# GlucometerV2_3.net
KiCad netlist of a schematic drawn in EAGLE
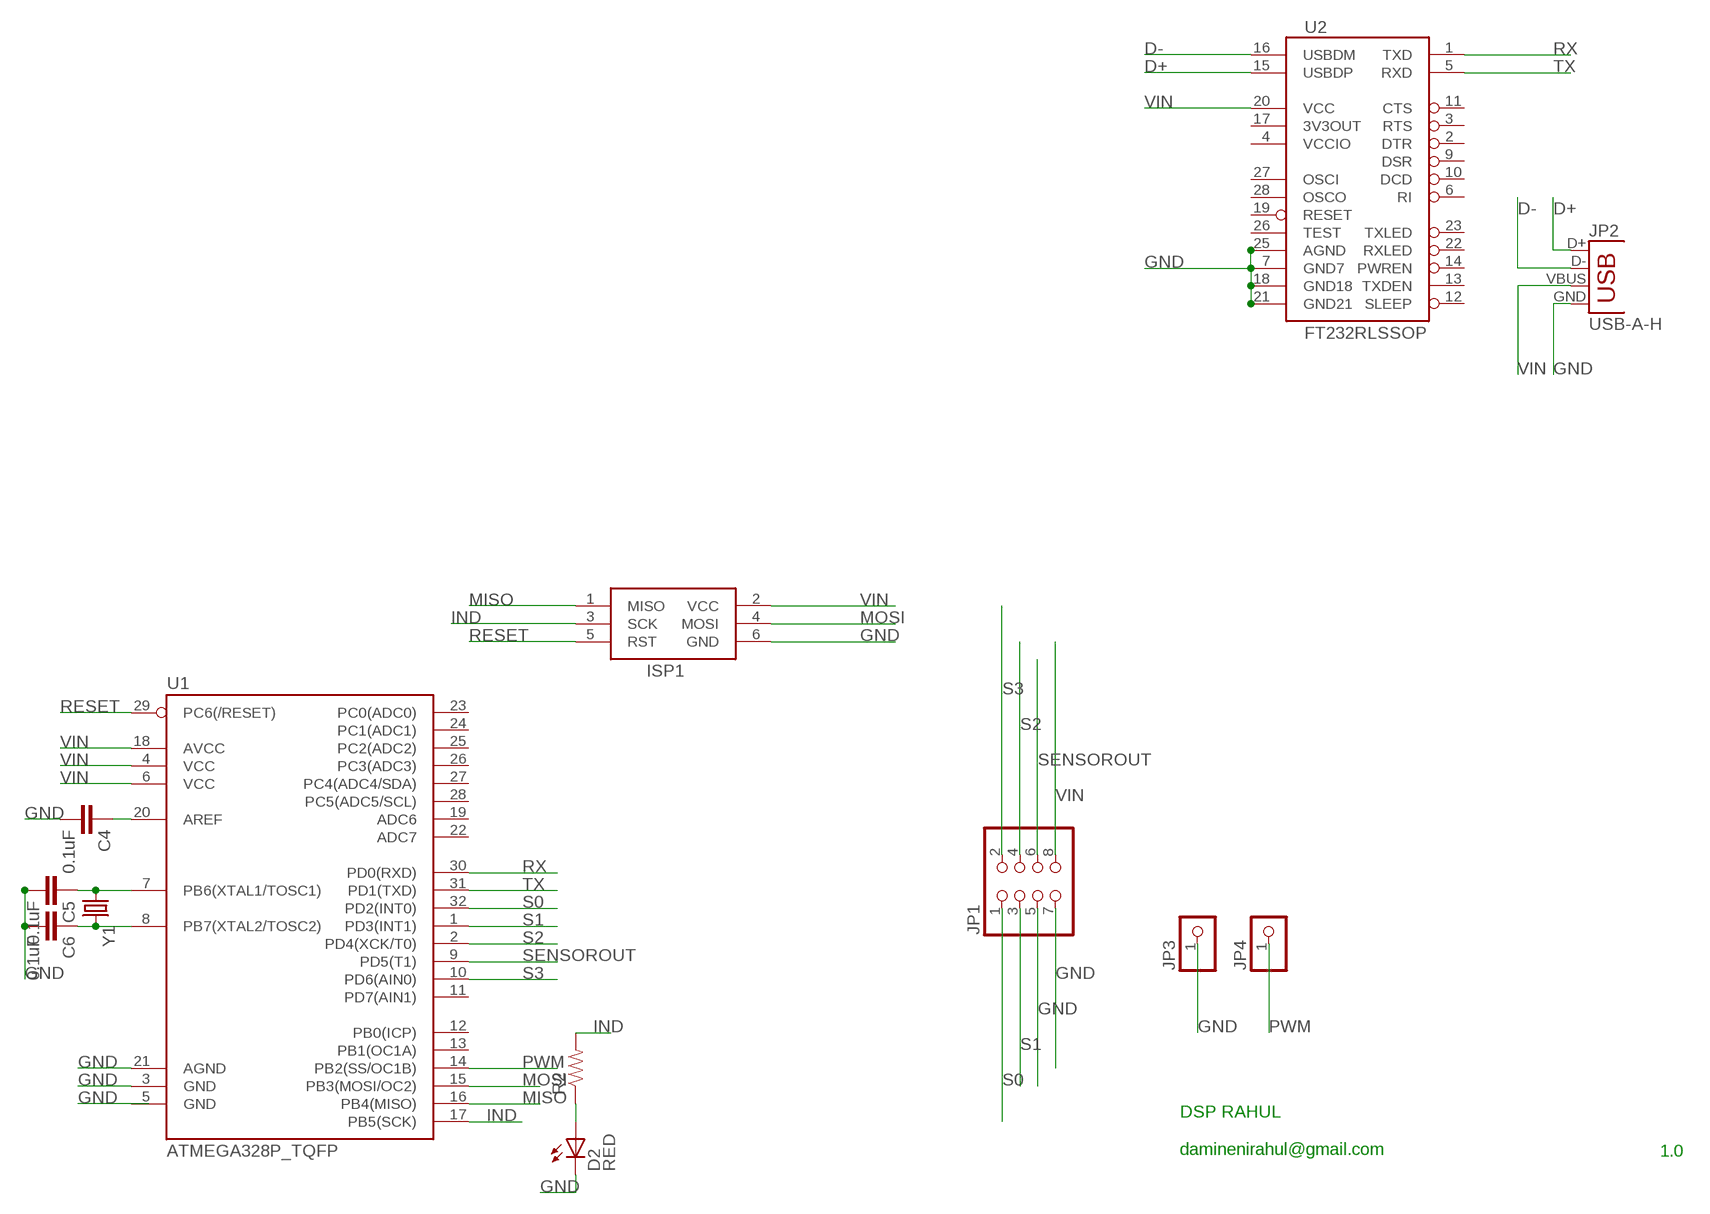
[diagram p0: schematic, sheet 1]

(export (version "E")
  (design (tool "Eeschema 10.0.6"))
  (components
    (comp (ref "C4")
      (value "0.1uF")
      (footprint "eagle-import:0603-CAP")
      (libsource (lib "eagle-import") (part "0.1UF-25V(+80/-20%)(0603)"))
    )
    (comp (ref "C5")
      (value "0.1uF")
      (footprint "eagle-import:0603-CAP")
      (libsource (lib "eagle-import") (part "0.1UF-25V(+80/-20%)(0603)"))
    )
    (comp (ref "C6")
      (value "0.1uF")
      (footprint "eagle-import:0603-CAP")
      (libsource (lib "eagle-import") (part "0.1UF-25V(+80/-20%)(0603)"))
    )
    (comp (ref "D2")
      (value "RED")
      (footprint "eagle-import:CHIPLED_1206")
      (libsource (lib "eagle-import") (part "LEDCHIPLED_1206"))
    )
    (comp (ref "ISP1")
      (value "AVRISP-6")
      (footprint "eagle-import:AVRISP")
      (libsource (lib "eagle-import") (part "AVRISP-6"))
    )
    (comp (ref "JP1")
      (value "PINHD-2X4")
      (footprint "eagle-import:2X04")
      (libsource (lib "eagle-import") (part "PINHD-2X4"))
    )
    (comp (ref "JP2")
      (value "USB-A-H")
      (footprint "eagle-import:USB-A-H")
      (libsource (lib "eagle-import") (part "USB-A-H"))
    )
    (comp (ref "JP3")
      (value "PINHD-1X1")
      (footprint "eagle-import:1X01")
      (libsource (lib "eagle-import") (part "PINHD-1X1"))
    )
    (comp (ref "JP4")
      (value "PINHD-1X1")
      (footprint "eagle-import:1X01")
      (libsource (lib "eagle-import") (part "PINHD-1X1"))
    )
    (comp (ref "R2")
      (value "RESISTOR1206")
      (footprint "eagle-import:1206")
      (libsource (lib "eagle-import") (part "RESISTOR1206"))
    )
    (comp (ref "U1")
      (value "ATMEGA328P_TQFP")
      (footprint "eagle-import:TQFP32-08")
      (libsource (lib "eagle-import") (part "ATMEGA328P_TQFP"))
    )
    (comp (ref "U2")
      (value "FT232RLSSOP")
      (footprint "eagle-import:SSOP28DB")
      (libsource (lib "eagle-import") (part "FT232RLSSOP"))
    )
    (comp (ref "Y1")
      (value "CRYSTALHC49UV")
      (footprint "eagle-import:HC49U-V")
      (libsource (lib "eagle-import") (part "CRYSTALHC49UV"))
    )
  )
  (nets
    (net (code "1") (name "/D+") (class "Default")
      (node (ref "JP2") (pin "D+") (pinfunction "D+_D+") (pintype "bidirectional"))
      (node (ref "U2") (pin "15") (pinfunction "USBDP_15") (pintype "bidirectional"))
    )
    (net (code "2") (name "/D-") (class "Default")
      (node (ref "JP2") (pin "D-") (pinfunction "D-_D-") (pintype "bidirectional"))
      (node (ref "U2") (pin "16") (pinfunction "USBDM_16") (pintype "bidirectional"))
    )
    (net (code "3") (name "/GND") (class "Default")
      (node (ref "C4") (pin "2") (pinfunction "2_2") (pintype "passive"))
      (node (ref "C5") (pin "2") (pinfunction "2_2") (pintype "passive"))
      (node (ref "C6") (pin "2") (pinfunction "2_2") (pintype "passive"))
      (node (ref "D2") (pin "C") (pinfunction "C_C") (pintype "passive"))
      (node (ref "ISP1") (pin "6") (pinfunction "GND_6") (pintype "power_in"))
      (node (ref "JP1") (pin "5") (pinfunction "5_5") (pintype "passive"))
      (node (ref "JP1") (pin "7") (pinfunction "7_7") (pintype "passive"))
      (node (ref "JP2") (pin "GND") (pinfunction "GND_GND") (pintype "bidirectional"))
      (node (ref "JP3") (pin "1") (pinfunction "1_1") (pintype "passive"))
      (node (ref "U1") (pin "21") (pinfunction "AGND_21") (pintype "bidirectional"))
      (node (ref "U1") (pin "3") (pinfunction "GND_3") (pintype "bidirectional"))
      (node (ref "U2") (pin "18") (pinfunction "GND18_18") (pintype "power_in"))
      (node (ref "U2") (pin "21") (pinfunction "GND21_21") (pintype "power_in"))
      (node (ref "U2") (pin "25") (pinfunction "AGND_25") (pintype "power_in"))
      (node (ref "U2") (pin "7") (pinfunction "GND7_7") (pintype "power_in"))
    )
    (net (code "4") (name "/IND") (class "Default")
      (node (ref "ISP1") (pin "3") (pinfunction "SCK_3") (pintype "output"))
      (node (ref "R2") (pin "2") (pinfunction "2_2") (pintype "passive"))
      (node (ref "U1") (pin "17") (pinfunction "PB5(SCK)_17") (pintype "bidirectional"))
    )
    (net (code "5") (name "/MISO") (class "Default")
      (node (ref "ISP1") (pin "1") (pinfunction "MISO_1") (pintype "input"))
      (node (ref "U1") (pin "16") (pinfunction "PB4(MISO)_16") (pintype "bidirectional"))
    )
    (net (code "6") (name "/MOSI") (class "Default")
      (node (ref "ISP1") (pin "4") (pinfunction "MOSI_4") (pintype "output"))
      (node (ref "U1") (pin "15") (pinfunction "PB3(MOSI/OC2)_15") (pintype "bidirectional"))
    )
    (net (code "7") (name "/PWM") (class "Default")
      (node (ref "JP4") (pin "1") (pinfunction "1_1") (pintype "passive"))
      (node (ref "U1") (pin "14") (pinfunction "PB2(SS/OC1B)_14") (pintype "bidirectional"))
    )
    (net (code "8") (name "/RESET") (class "Default")
      (node (ref "ISP1") (pin "5") (pinfunction "RST_5") (pintype "output"))
      (node (ref "U1") (pin "29") (pinfunction "PC6(/RESET)_29") (pintype "bidirectional"))
    )
    (net (code "9") (name "/RX") (class "Default")
      (node (ref "U1") (pin "30") (pinfunction "PD0(RXD)_30") (pintype "bidirectional"))
      (node (ref "U2") (pin "1") (pinfunction "TXD_1") (pintype "output"))
    )
    (net (code "10") (name "/S0") (class "Default")
      (node (ref "JP1") (pin "1") (pinfunction "1_1") (pintype "passive"))
      (node (ref "U1") (pin "32") (pinfunction "PD2(INT0)_32") (pintype "bidirectional"))
    )
    (net (code "11") (name "/S1") (class "Default")
      (node (ref "JP1") (pin "3") (pinfunction "3_3") (pintype "passive"))
      (node (ref "U1") (pin "1") (pinfunction "PD3(INT1)_1") (pintype "bidirectional"))
    )
    (net (code "12") (name "/S2") (class "Default")
      (node (ref "JP1") (pin "4") (pinfunction "4_4") (pintype "passive"))
      (node (ref "U1") (pin "2") (pinfunction "PD4(XCK/T0)_2") (pintype "bidirectional"))
    )
    (net (code "13") (name "/S3") (class "Default")
      (node (ref "JP1") (pin "2") (pinfunction "2_2") (pintype "passive"))
      (node (ref "U1") (pin "10") (pinfunction "PD6(AIN0)_10") (pintype "bidirectional"))
    )
    (net (code "14") (name "/SENSOROUT") (class "Default")
      (node (ref "JP1") (pin "6") (pinfunction "6_6") (pintype "passive"))
      (node (ref "U1") (pin "9") (pinfunction "PD5(T1)_9") (pintype "bidirectional"))
    )
    (net (code "15") (name "/TX") (class "Default")
      (node (ref "U1") (pin "31") (pinfunction "PD1(TXD)_31") (pintype "bidirectional"))
      (node (ref "U2") (pin "5") (pinfunction "RXD_5") (pintype "input"))
    )
    (net (code "16") (name "/VCCIO") (class "Default")
      (node (ref "U2") (pin "4") (pinfunction "VCCIO_4") (pintype "power_in"))
    )
    (net (code "17") (name "/VIN") (class "Default")
      (node (ref "ISP1") (pin "2") (pinfunction "VCC_2") (pintype "power_in"))
      (node (ref "JP1") (pin "8") (pinfunction "8_8") (pintype "passive"))
      (node (ref "JP2") (pin "VBUS") (pinfunction "VBUS_VBUS") (pintype "bidirectional"))
      (node (ref "U1") (pin "18") (pinfunction "AVCC_18") (pintype "bidirectional"))
      (node (ref "U1") (pin "4") (pinfunction "VCC_4") (pintype "bidirectional"))
      (node (ref "U1") (pin "6") (pinfunction "VCC_6") (pintype "bidirectional"))
      (node (ref "U2") (pin "20") (pinfunction "VCC_20") (pintype "power_in"))
    )
    (net (code "18") (name "Net-(D2-PadA)") (class "Default")
      (node (ref "D2") (pin "A") (pinfunction "A_A") (pintype "passive"))
      (node (ref "R2") (pin "1") (pinfunction "1_1") (pintype "passive"))
    )
    (net (code "19") (name "Net-(U1-AREF)") (class "Default")
      (node (ref "C4") (pin "1") (pinfunction "1_1") (pintype "passive"))
      (node (ref "U1") (pin "20") (pinfunction "AREF_20") (pintype "bidirectional"))
    )
    (net (code "20") (name "Net-(U1-PB6(XTAL1{slash}TOSC1))") (class "Default")
      (node (ref "C5") (pin "1") (pinfunction "1_1") (pintype "passive"))
      (node (ref "U1") (pin "7") (pinfunction "PB6(XTAL1/TOSC1)_7") (pintype "bidirectional"))
      (node (ref "Y1") (pin "1") (pinfunction "1_1") (pintype "passive"))
    )
    (net (code "21") (name "Net-(U1-PB7(XTAL2{slash}TOSC2))") (class "Default")
      (node (ref "C6") (pin "1") (pinfunction "1_1") (pintype "passive"))
      (node (ref "U1") (pin "8") (pinfunction "PB7(XTAL2/TOSC2)_8") (pintype "bidirectional"))
      (node (ref "Y1") (pin "2") (pinfunction "2_2") (pintype "passive"))
    )
    (net (code "22") (name "unconnected-(U1-ADC6-Pad19)") (class "Default")
      (node (ref "U1") (pin "19") (pinfunction "ADC6_19") (pintype "bidirectional"))
    )
    (net (code "23") (name "unconnected-(U1-ADC7-Pad22)") (class "Default")
      (node (ref "U1") (pin "22") (pinfunction "ADC7_22") (pintype "bidirectional"))
    )
    (net (code "24") (name "unconnected-(U1-GND-Pad5)") (class "Default")
      (node (ref "U1") (pin "5") (pinfunction "GND_5") (pintype "bidirectional"))
    )
    (net (code "25") (name "unconnected-(U1-PB0(ICP)-Pad12)") (class "Default")
      (node (ref "U1") (pin "12") (pinfunction "PB0(ICP)_12") (pintype "bidirectional"))
    )
    (net (code "26") (name "unconnected-(U1-PB1(OC1A)-Pad13)") (class "Default")
      (node (ref "U1") (pin "13") (pinfunction "PB1(OC1A)_13") (pintype "bidirectional"))
    )
    (net (code "27") (name "unconnected-(U1-PC0(ADC0)-Pad23)") (class "Default")
      (node (ref "U1") (pin "23") (pinfunction "PC0(ADC0)_23") (pintype "bidirectional"))
    )
    (net (code "28") (name "unconnected-(U1-PC1(ADC1)-Pad24)") (class "Default")
      (node (ref "U1") (pin "24") (pinfunction "PC1(ADC1)_24") (pintype "bidirectional"))
    )
    (net (code "29") (name "unconnected-(U1-PC2(ADC2)-Pad25)") (class "Default")
      (node (ref "U1") (pin "25") (pinfunction "PC2(ADC2)_25") (pintype "bidirectional"))
    )
    (net (code "30") (name "unconnected-(U1-PC3(ADC3)-Pad26)") (class "Default")
      (node (ref "U1") (pin "26") (pinfunction "PC3(ADC3)_26") (pintype "bidirectional"))
    )
    (net (code "31") (name "unconnected-(U1-PC4(ADC4{slash}SDA)-Pad27)") (class "Default")
      (node (ref "U1") (pin "27") (pinfunction "PC4(ADC4/SDA)_27") (pintype "bidirectional"))
    )
    (net (code "32") (name "unconnected-(U1-PC5(ADC5{slash}SCL)-Pad28)") (class "Default")
      (node (ref "U1") (pin "28") (pinfunction "PC5(ADC5/SCL)_28") (pintype "bidirectional"))
    )
    (net (code "33") (name "unconnected-(U1-PD7(AIN1)-Pad11)") (class "Default")
      (node (ref "U1") (pin "11") (pinfunction "PD7(AIN1)_11") (pintype "bidirectional"))
    )
    (net (code "34") (name "unconnected-(U2-3V3OUT-Pad17)") (class "Default")
      (node (ref "U2") (pin "17") (pinfunction "3V3OUT_17") (pintype "output"))
    )
    (net (code "35") (name "unconnected-(U2-CTS-Pad11)") (class "Default")
      (node (ref "U2") (pin "11") (pinfunction "CTS_11") (pintype "input"))
    )
    (net (code "36") (name "unconnected-(U2-DCD-Pad10)") (class "Default")
      (node (ref "U2") (pin "10") (pinfunction "DCD_10") (pintype "input"))
    )
    (net (code "37") (name "unconnected-(U2-DSR-Pad9)") (class "Default")
      (node (ref "U2") (pin "9") (pinfunction "DSR_9") (pintype "input"))
    )
    (net (code "38") (name "unconnected-(U2-DTR-Pad2)") (class "Default")
      (node (ref "U2") (pin "2") (pinfunction "DTR_2") (pintype "output"))
    )
    (net (code "39") (name "unconnected-(U2-OSCI-Pad27)") (class "Default")
      (node (ref "U2") (pin "27") (pinfunction "OSCI_27") (pintype "input"))
    )
    (net (code "40") (name "unconnected-(U2-OSCO-Pad28)") (class "Default")
      (node (ref "U2") (pin "28") (pinfunction "OSCO_28") (pintype "output"))
    )
    (net (code "41") (name "unconnected-(U2-PWREN-Pad14)") (class "Default")
      (node (ref "U2") (pin "14") (pinfunction "PWREN_14") (pintype "input"))
    )
    (net (code "42") (name "unconnected-(U2-RESET-Pad19)") (class "Default")
      (node (ref "U2") (pin "19") (pinfunction "RESET_19") (pintype "input"))
    )
    (net (code "43") (name "unconnected-(U2-RI-Pad6)") (class "Default")
      (node (ref "U2") (pin "6") (pinfunction "RI_6") (pintype "input"))
    )
    (net (code "44") (name "unconnected-(U2-RTS-Pad3)") (class "Default")
      (node (ref "U2") (pin "3") (pinfunction "RTS_3") (pintype "output"))
    )
    (net (code "45") (name "unconnected-(U2-RXLED-Pad22)") (class "Default")
      (node (ref "U2") (pin "22") (pinfunction "RXLED_22") (pintype "input"))
    )
    (net (code "46") (name "unconnected-(U2-SLEEP-Pad12)") (class "Default")
      (node (ref "U2") (pin "12") (pinfunction "SLEEP_12") (pintype "input"))
    )
    (net (code "47") (name "unconnected-(U2-TEST-Pad26)") (class "Default")
      (node (ref "U2") (pin "26") (pinfunction "TEST_26") (pintype "input"))
    )
    (net (code "48") (name "unconnected-(U2-TXDEN-Pad13)") (class "Default")
      (node (ref "U2") (pin "13") (pinfunction "TXDEN_13") (pintype "input"))
    )
    (net (code "49") (name "unconnected-(U2-TXLED-Pad23)") (class "Default")
      (node (ref "U2") (pin "23") (pinfunction "TXLED_23") (pintype "input"))
    )
  )
)
